# avalanche_PSU.net
KiCad netlist of a schematic drawn in EAGLE
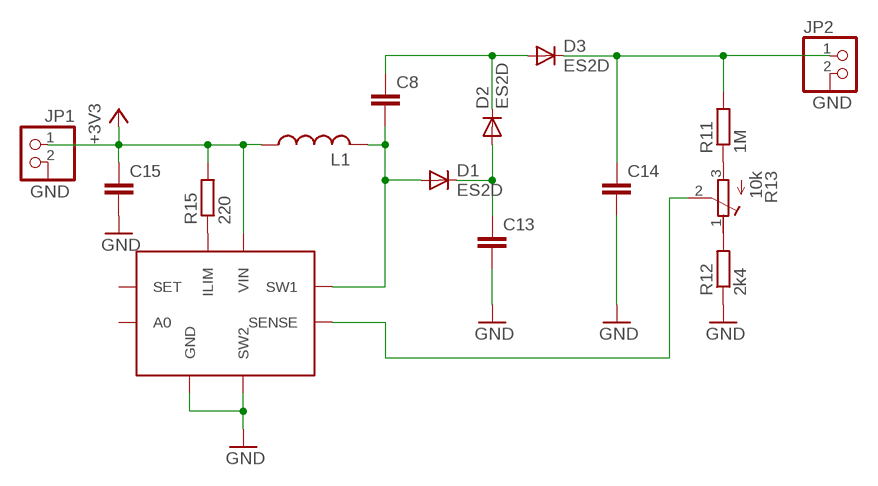
[diagram p0: schematic, sheet 1]

(export (version "E")
  (design (tool "Eeschema 10.0.6"))
  (components
    (comp (ref "C8")
      (value "C-EUC0805K")
      (footprint "eagle-import:C0805K")
      (libsource (lib "eagle-import") (part "C-EUC0805K"))
    )
    (comp (ref "C13")
      (value "C-EUC0805K")
      (footprint "eagle-import:C0805K")
      (libsource (lib "eagle-import") (part "C-EUC0805K"))
    )
    (comp (ref "C14")
      (value "C-EUC0805K")
      (footprint "eagle-import:C0805K")
      (libsource (lib "eagle-import") (part "C-EUC0805K"))
    )
    (comp (ref "C15")
      (value "C-EUC1206")
      (footprint "eagle-import:C1206")
      (libsource (lib "eagle-import") (part "C-EUC1206"))
    )
    (comp (ref "D1")
      (value "ES2D")
      (footprint "eagle-import:SMB")
      (libsource (lib "eagle-import") (part "ES2D"))
    )
    (comp (ref "D2")
      (value "ES2D")
      (footprint "eagle-import:SMB")
      (libsource (lib "eagle-import") (part "ES2D"))
    )
    (comp (ref "D3")
      (value "ES2D")
      (footprint "eagle-import:SMB")
      (libsource (lib "eagle-import") (part "ES2D"))
    )
    (comp (ref "JP1")
      (value "PINHD-1X2")
      (footprint "eagle-import:1X02")
      (libsource (lib "eagle-import") (part "PINHD-1X2"))
    )
    (comp (ref "JP2")
      (value "PINHD-1X2")
      (footprint "eagle-import:1X02")
      (libsource (lib "eagle-import") (part "PINHD-1X2"))
    )
    (comp (ref "L1")
      (value "L-US")
      (footprint "eagle-import:SRR1280")
      (libsource (lib "eagle-import") (part "L-US"))
    )
    (comp (ref "R11")
      (value "1M")
      (footprint "eagle-import:M0805")
      (libsource (lib "eagle-import") (part "R-EU_M0805"))
    )
    (comp (ref "R12")
      (value "2k4")
      (footprint "eagle-import:M0805")
      (libsource (lib "eagle-import") (part "R-EU_M0805"))
    )
    (comp (ref "R13")
      (value "10k")
      (footprint "eagle-import:RTRIMT18")
      (libsource (lib "eagle-import") (part "R-TRIMMT18"))
    )
    (comp (ref "R15")
      (value "220")
      (footprint "eagle-import:M0805")
      (libsource (lib "eagle-import") (part "R-EU_M0805"))
    )
    (comp (ref "U$3")
      (value "LT1073")
      (footprint "eagle-import:DIL08")
      (libsource (lib "eagle-import") (part "LT1073"))
    )
  )
  (nets
    (net (code "1") (name "+3V3") (class "Default")
      (node (ref "C15") (pin "1") (pinfunction "1_1") (pintype "passive"))
      (node (ref "JP1") (pin "1") (pinfunction "1_1") (pintype "passive"))
      (node (ref "L1") (pin "P$1") (pinfunction "1_P$1") (pintype "passive"))
      (node (ref "R15") (pin "2") (pinfunction "2_2") (pintype "passive"))
      (node (ref "U$3") (pin "2") (pinfunction "VIN_2") (pintype "bidirectional"))
    )
    (net (code "2") (name "GND") (class "Default")
      (node (ref "C13") (pin "2") (pinfunction "2_2") (pintype "passive"))
      (node (ref "C14") (pin "2") (pinfunction "2_2") (pintype "passive"))
      (node (ref "C15") (pin "2") (pinfunction "2_2") (pintype "passive"))
      (node (ref "JP1") (pin "2") (pinfunction "2_2") (pintype "passive"))
      (node (ref "JP2") (pin "2") (pinfunction "2_2") (pintype "passive"))
      (node (ref "R12") (pin "1") (pinfunction "1_1") (pintype "passive"))
      (node (ref "U$3") (pin "4") (pinfunction "SW2_4") (pintype "bidirectional"))
      (node (ref "U$3") (pin "5") (pinfunction "GND_5") (pintype "bidirectional"))
    )
    (net (code "3") (name "Net-(C8-Pad1)") (class "Default")
      (node (ref "C8") (pin "1") (pinfunction "1_1") (pintype "passive"))
      (node (ref "D2") (pin "C") (pinfunction "C_C") (pintype "passive"))
      (node (ref "D3") (pin "A") (pinfunction "A_A") (pintype "passive"))
    )
    (net (code "4") (name "Net-(C13-Pad1)") (class "Default")
      (node (ref "C13") (pin "1") (pinfunction "1_1") (pintype "passive"))
      (node (ref "D1") (pin "C") (pinfunction "C_C") (pintype "passive"))
      (node (ref "D2") (pin "A") (pinfunction "A_A") (pintype "passive"))
    )
    (net (code "5") (name "Net-(C14-Pad1)") (class "Default")
      (node (ref "C14") (pin "1") (pinfunction "1_1") (pintype "passive"))
      (node (ref "D3") (pin "C") (pinfunction "C_C") (pintype "passive"))
      (node (ref "JP2") (pin "1") (pinfunction "1_1") (pintype "passive"))
      (node (ref "R11") (pin "2") (pinfunction "2_2") (pintype "passive"))
    )
    (net (code "6") (name "Net-(L1-2)") (class "Default")
      (node (ref "C8") (pin "2") (pinfunction "2_2") (pintype "passive"))
      (node (ref "D1") (pin "A") (pinfunction "A_A") (pintype "passive"))
      (node (ref "L1") (pin "P$2") (pinfunction "2_P$2") (pintype "passive"))
      (node (ref "U$3") (pin "3") (pinfunction "SW1_3") (pintype "bidirectional"))
    )
    (net (code "7") (name "Net-(R13-A)") (class "Default")
      (node (ref "R12") (pin "2") (pinfunction "2_2") (pintype "passive"))
      (node (ref "R13") (pin "1") (pinfunction "A_1") (pintype "passive"))
    )
    (net (code "8") (name "Net-(R13-E)") (class "Default")
      (node (ref "R11") (pin "1") (pinfunction "1_1") (pintype "passive"))
      (node (ref "R13") (pin "3") (pinfunction "E_3") (pintype "passive"))
    )
    (net (code "9") (name "Net-(R13-S)") (class "Default")
      (node (ref "R13") (pin "2") (pinfunction "S_2") (pintype "passive"))
      (node (ref "U$3") (pin "8") (pinfunction "SENSE_8") (pintype "bidirectional"))
    )
    (net (code "10") (name "Net-(U$3-ILIM)") (class "Default")
      (node (ref "R15") (pin "1") (pinfunction "1_1") (pintype "passive"))
      (node (ref "U$3") (pin "1") (pinfunction "ILIM_1") (pintype "bidirectional"))
    )
    (net (code "11") (name "unconnected-(U$3-A0-Pad6)") (class "Default")
      (node (ref "U$3") (pin "6") (pinfunction "A0_6") (pintype "bidirectional"))
    )
    (net (code "12") (name "unconnected-(U$3-SET-Pad7)") (class "Default")
      (node (ref "U$3") (pin "7") (pinfunction "SET_7") (pintype "bidirectional"))
    )
  )
)
